# MP2019_LDO_5V.net
KiCad netlist of a schematic drawn in Altium Designer
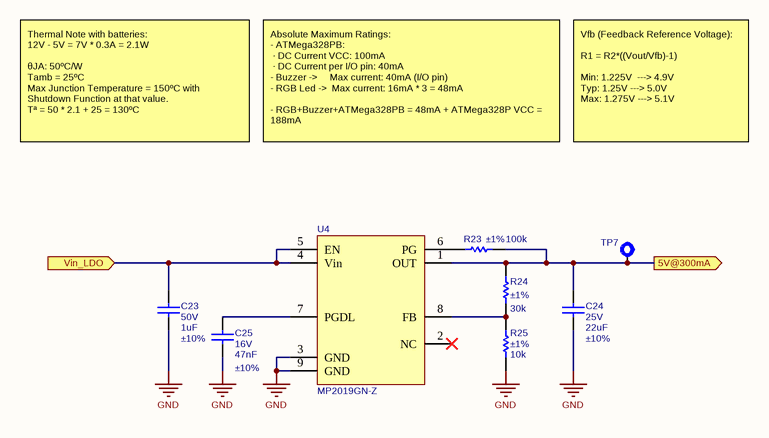
[diagram p0: MP2019_LDO_5V.SchDoc]

(export (version "E")
  (design (tool "Eeschema 10.0.6"))
  (components
    (comp (ref "C23")
      (value "C0805_1uF_50V_±10%_X7R")
      (footprint "C0805")
      (fields
        (field (name "VOLTAGE") "50V")
        (field (name "CAPACITANCE") "1uF")
        (field (name "TOLERANCE") "±10%")
        (field (name "MANUFACTURER") "Kemet")
      )
      (libsource (lib "BQ Vault") (part "Capacitor"))
    )
    (comp (ref "C24")
      (value "C1206_22uF_25V_±10%")
      (footprint "C1206")
      (fields
        (field (name "VOLTAGE") "25V")
        (field (name "CAPACITANCE") "22uF")
        (field (name "TOLERANCE") "±10%")
        (field (name "MANUFACTURER") "Murata")
      )
      (libsource (lib "BQ Vault") (part "Capacitor"))
    )
    (comp (ref "C25")
      (value "C0402_47nF_16V_±10%")
      (footprint "C0402")
      (fields
        (field (name "VOLTAGE") "16V")
        (field (name "CAPACITANCE") "47nF")
        (field (name "TOLERANCE") "±10%")
        (field (name "MANUFACTURER") "Kemet")
      )
      (libsource (lib "BQ Vault") (part "Capacitor"))
    )
    (comp (ref "R23")
      (value "R0402_100k_0.063W_±1%")
      (footprint "R0402")
      (fields
        (field (name "TOLERANCE") "±1%")
        (field (name "POWER") "0.063W")
        (field (name "RESISTANCE") "100k")
        (field (name "MANUFACTURER") "Vishay")
      )
      (libsource (lib "BQ Vault") (part "Resistor"))
    )
    (comp (ref "R24")
      (value "R0402_30k_0.063W_±1%")
      (footprint "R0402")
      (fields
        (field (name "TOLERANCE") "±1%")
        (field (name "POWER") "0.063W")
        (field (name "RESISTANCE") "30k")
        (field (name "MANUFACTURER") "Vishay")
      )
      (libsource (lib "BQ Vault") (part "Resistor"))
    )
    (comp (ref "R25")
      (value "R0402_10k_0.063W_±1%")
      (footprint "R0402")
      (fields
        (field (name "TOLERANCE") "±1%")
        (field (name "POWER") "0.063W")
        (field (name "RESISTANCE") "10k")
        (field (name "MANUFACTURER") "Vishay")
      )
      (libsource (lib "BQ Vault") (part "Resistor"))
    )
    (comp (ref "TP7")
      (value "TP")
      (footprint "TP_POWER")
      (description "Testpoint 0.3mm")
      (fields (field (name "MANUFACTURER") "Oxley") (field (name "PART NUMBER") "TP_POWER"))
      (libsource (lib "BQ Vault") (part "CMP-A2499-3"))
    )
    (comp (ref "U4")
      (value "MP2019GN-Z")
      (footprint "SOIC8 EP")
      (description "LDO Vin: 3-40V Vout: 1.2-15V @300mA")
      (fields (field (name "MANUFACTURER") "Monolithic Power Systems"))
      (libsource (lib "BQ Vault") (part "MP2019"))
    )
  )
  (nets
    (net (code "1") (name "/5V@300mA") (class "Default")
      (node (ref "C24") (pin "2") (pinfunction "2_2") (pintype "passive"))
      (node (ref "R23") (pin "1") (pinfunction "1_1") (pintype "passive"))
      (node (ref "R24") (pin "2") (pinfunction "2_2") (pintype "passive"))
      (node (ref "TP7") (pin "1") (pinfunction "1_1") (pintype "passive"))
      (node (ref "U4") (pin "1") (pinfunction "OUT_1") (pintype "passive"))
    )
    (net (code "2") (name "/Vin_LDO") (class "Default")
      (node (ref "C23") (pin "2") (pinfunction "2_2") (pintype "passive"))
      (node (ref "U4") (pin "4") (pinfunction "Vin_4") (pintype "passive"))
      (node (ref "U4") (pin "5") (pinfunction "EN_5") (pintype "passive"))
    )
    (net (code "3") (name "GND") (class "Default")
      (node (ref "C23") (pin "1") (pinfunction "1_1") (pintype "passive"))
      (node (ref "C24") (pin "1") (pinfunction "1_1") (pintype "passive"))
      (node (ref "C25") (pin "1") (pinfunction "1_1") (pintype "passive"))
      (node (ref "R25") (pin "2") (pinfunction "2_2") (pintype "passive"))
      (node (ref "U4") (pin "3") (pinfunction "GND_3") (pintype "passive"))
      (node (ref "U4") (pin "9") (pinfunction "GND_9") (pintype "passive"))
    )
    (net (code "4") (name "Net-(U4-FB)") (class "Default")
      (node (ref "R24") (pin "1") (pinfunction "1_1") (pintype "passive"))
      (node (ref "R25") (pin "1") (pinfunction "1_1") (pintype "passive"))
      (node (ref "U4") (pin "8") (pinfunction "FB_8") (pintype "passive"))
    )
    (net (code "5") (name "Net-(U4-PG)") (class "Default")
      (node (ref "R23") (pin "2") (pinfunction "2_2") (pintype "passive"))
      (node (ref "U4") (pin "6") (pinfunction "PG_6") (pintype "passive"))
    )
    (net (code "6") (name "Net-(U4-PGDL)") (class "Default")
      (node (ref "C25") (pin "2") (pinfunction "2_2") (pintype "passive"))
      (node (ref "U4") (pin "7") (pinfunction "PGDL_7") (pintype "passive"))
    )
    (net (code "7") (name "unconnected-(U4-NC-Pad2)") (class "Default")
      (node (ref "U4") (pin "2") (pinfunction "NC_2") (pintype "passive+no_connect"))
    )
  )
)
